# Light_Ctrol.net
KiCad netlist of a schematic drawn in Altium Designer
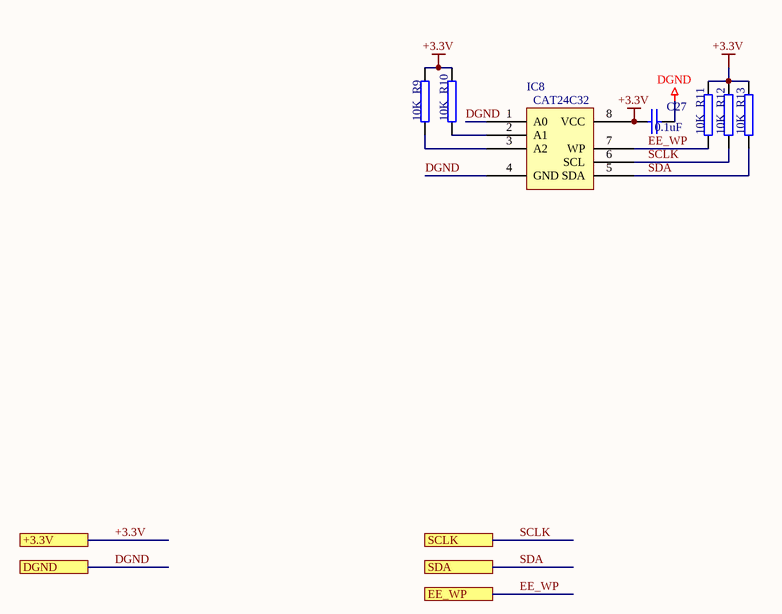
[diagram p0: Light_Ctrol.SchDoc]

(export (version "E")
  (design (tool "Eeschema 10.0.6"))
  (components
    (comp (ref "C27")
      (value "0.1uF")
      (footprint "0805C")
      (description "Capacitor")
      (libsource (lib "*") (part "CAP"))
    )
    (comp (ref "IC8") (value "CAT24C32") (footprint "SO8") (libsource (lib "*") (part "CAT24C32")))
    (comp (ref "R9")
      (value "10K")
      (footprint "0805R")
      (description "品牌： UNI-ROYAL(厚声) 型号： 0805W8F1002T5E 电阻类型：厚膜电阻 阻值：10kΩ 精度：±1% 功率：125mW 温度系数：±100ppm/℃")
      (libsource (lib "*") (part "RES2"))
    )
    (comp (ref "R10")
      (value "10K")
      (footprint "0805R")
      (description "品牌： UNI-ROYAL(厚声) 型号： 0805W8F1002T5E 电阻类型：厚膜电阻 阻值：10kΩ 精度：±1% 功率：125mW 温度系数：±100ppm/℃")
      (libsource (lib "*") (part "RES2"))
    )
    (comp (ref "R11")
      (value "10K")
      (footprint "0805R")
      (description "品牌： UNI-ROYAL(厚声) 型号： 0805W8F1002T5E 电阻类型：厚膜电阻 阻值：10kΩ 精度：±1% 功率：125mW 温度系数：±100ppm/℃")
      (libsource (lib "*") (part "RES2"))
    )
    (comp (ref "R12")
      (value "10K")
      (footprint "0805R")
      (description "品牌： UNI-ROYAL(厚声) 型号： 0805W8F1002T5E 电阻类型：厚膜电阻 阻值：10kΩ 精度：±1% 功率：125mW 温度系数：±100ppm/℃")
      (libsource (lib "*") (part "RES2"))
    )
    (comp (ref "R13")
      (value "10K")
      (footprint "0805R")
      (description "品牌： UNI-ROYAL(厚声) 型号： 0805W8F1002T5E 电阻类型：厚膜电阻 阻值：10kΩ 精度：±1% 功率：125mW 温度系数：±100ppm/℃")
      (libsource (lib "*") (part "RES2"))
    )
  )
  (nets
    (net (code "1") (name "+3.3V") (class "Default")
      (node (ref "C27") (pin "2") (pinfunction "2_2") (pintype "passive"))
      (node (ref "IC8") (pin "8") (pinfunction "VCC_8") (pintype "passive"))
      (node (ref "R10") (pin "1") (pinfunction "1_1") (pintype "passive"))
      (node (ref "R11") (pin "1") (pinfunction "1_1") (pintype "passive"))
      (node (ref "R12") (pin "1") (pinfunction "1_1") (pintype "passive"))
      (node (ref "R13") (pin "1") (pinfunction "1_1") (pintype "passive"))
      (node (ref "R9") (pin "1") (pinfunction "1_1") (pintype "passive"))
    )
    (net (code "2") (name "/EE_WP") (class "Default")
      (node (ref "IC8") (pin "7") (pinfunction "WP_7") (pintype "passive"))
      (node (ref "R11") (pin "2") (pinfunction "2_2") (pintype "passive"))
    )
    (net (code "3") (name "/SCLK") (class "Default")
      (node (ref "IC8") (pin "6") (pinfunction "SCL_6") (pintype "passive"))
      (node (ref "R12") (pin "2") (pinfunction "2_2") (pintype "passive"))
    )
    (net (code "4") (name "/SDA") (class "Default")
      (node (ref "IC8") (pin "5") (pinfunction "SDA_5") (pintype "passive"))
      (node (ref "R13") (pin "2") (pinfunction "2_2") (pintype "passive"))
    )
    (net (code "5") (name "DGND") (class "Default")
      (node (ref "C27") (pin "1") (pinfunction "1_1") (pintype "passive"))
      (node (ref "IC8") (pin "1") (pinfunction "A0_1") (pintype "passive"))
      (node (ref "IC8") (pin "4") (pinfunction "GND_4") (pintype "passive"))
    )
    (net (code "6") (name "Net-(IC8-A1)") (class "Default")
      (node (ref "IC8") (pin "2") (pinfunction "A1_2") (pintype "passive"))
      (node (ref "R10") (pin "2") (pinfunction "2_2") (pintype "passive"))
    )
    (net (code "7") (name "Net-(IC8-A2)") (class "Default")
      (node (ref "IC8") (pin "3") (pinfunction "A2_3") (pintype "passive"))
      (node (ref "R9") (pin "2") (pinfunction "2_2") (pintype "passive"))
    )
  )
)
